# RJ45LVDS_SPI.net
KiCad netlist of a schematic drawn in EAGLE
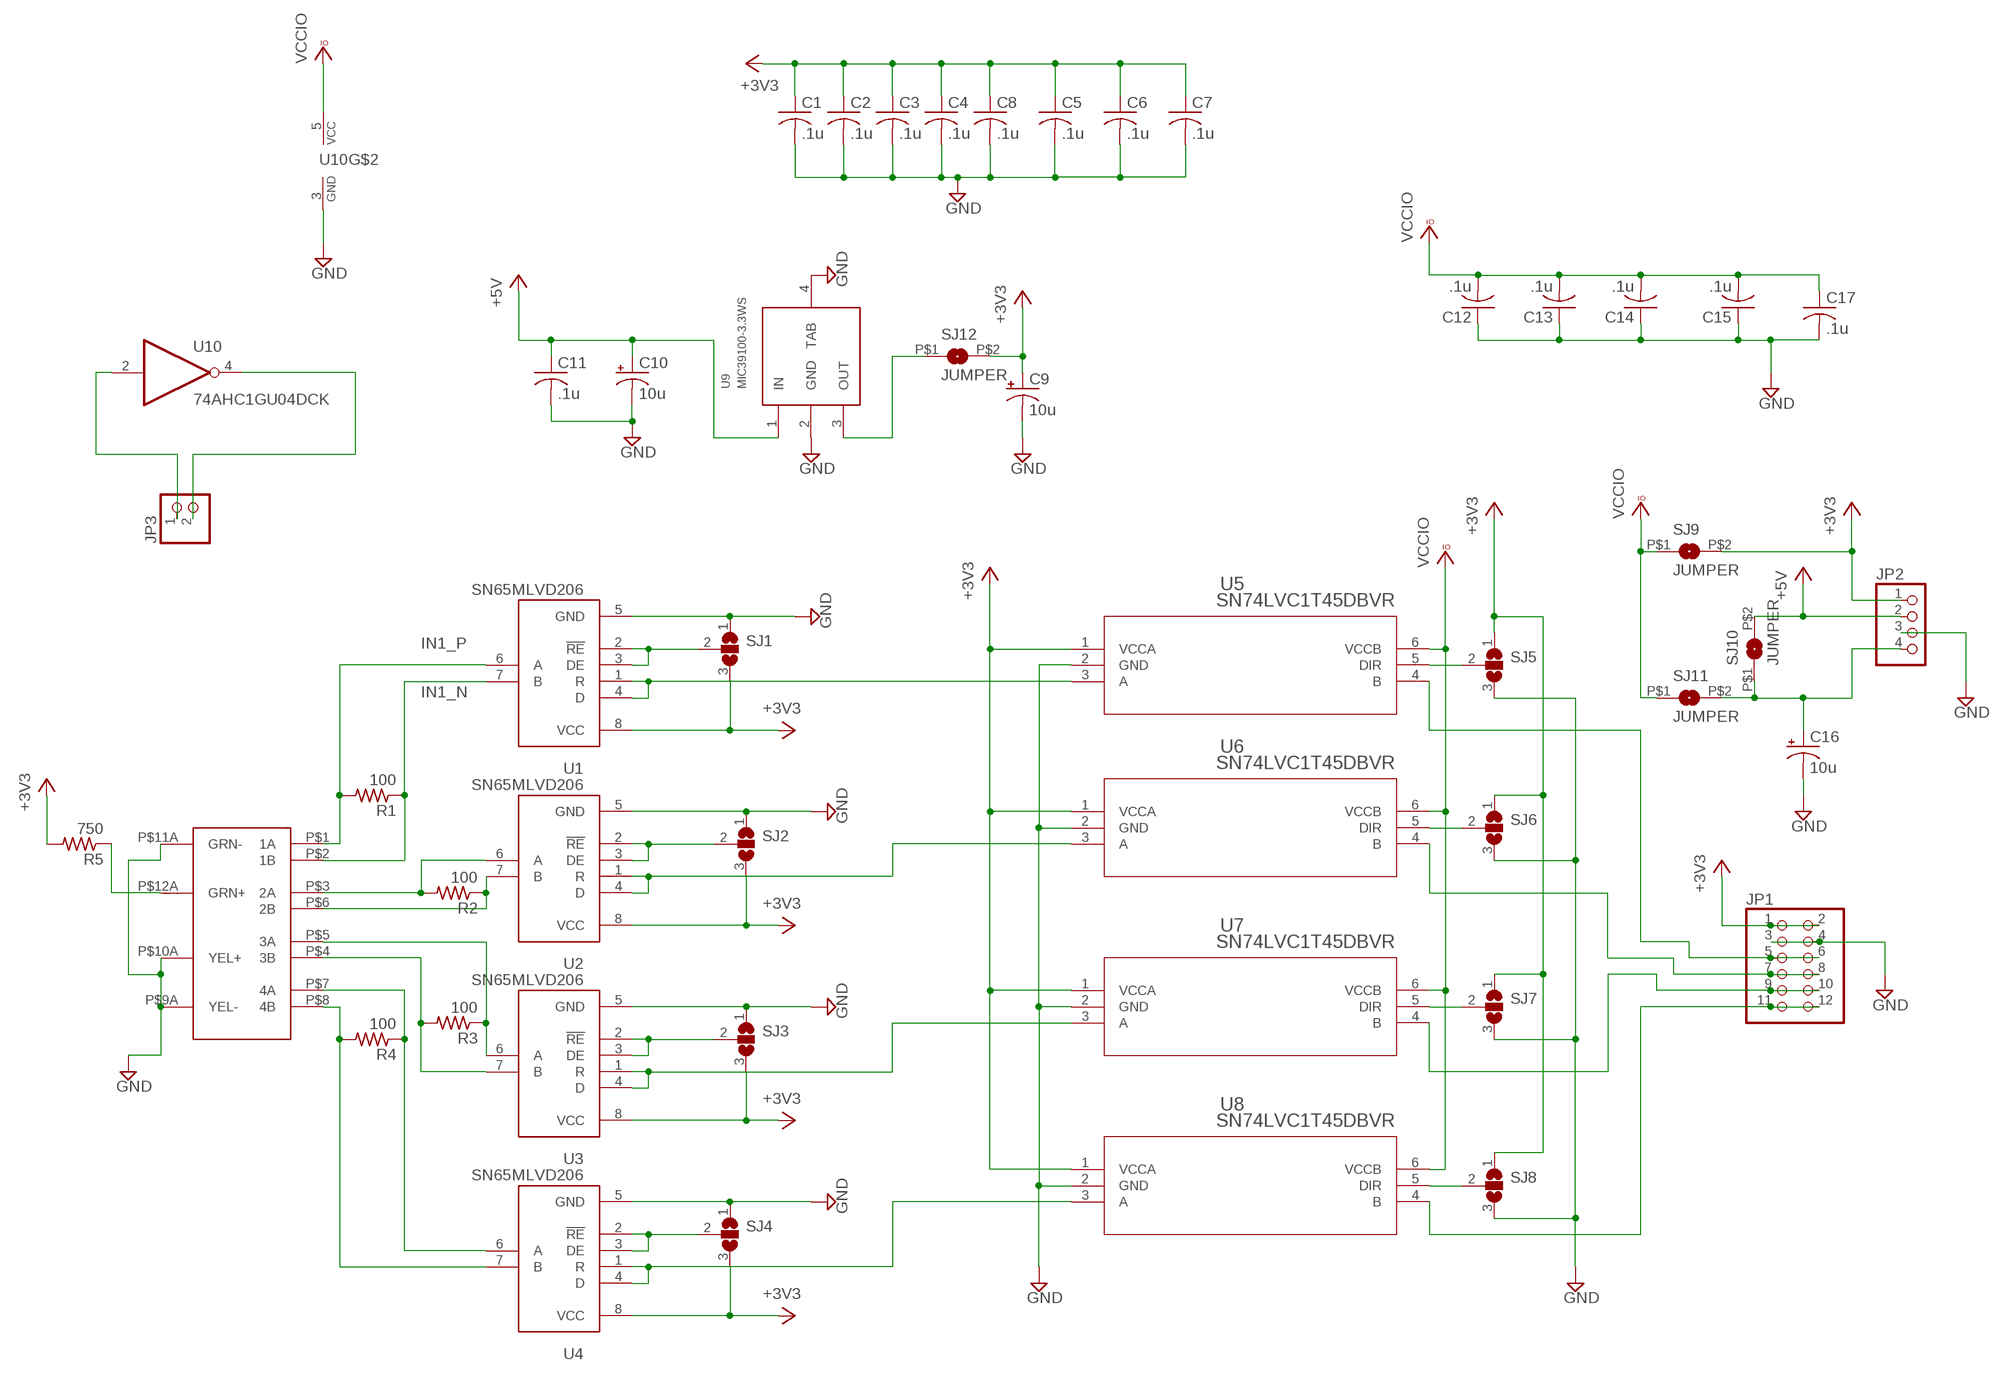
[diagram p0: schematic, sheet 1]

(export (version "E")
  (design (tool "Eeschema 10.0.6"))
  (components
    (comp (ref "C1")
      (value ".1u")
      (footprint "eagle-import:C0603")
      (libsource (lib "eagle-import") (part "C-USC0603"))
    )
    (comp (ref "C2")
      (value ".1u")
      (footprint "eagle-import:C0603")
      (libsource (lib "eagle-import") (part "C-USC0603"))
    )
    (comp (ref "C3")
      (value ".1u")
      (footprint "eagle-import:C0603")
      (libsource (lib "eagle-import") (part "C-USC0603"))
    )
    (comp (ref "C4")
      (value ".1u")
      (footprint "eagle-import:C0603")
      (libsource (lib "eagle-import") (part "C-USC0603"))
    )
    (comp (ref "C5")
      (value ".1u")
      (footprint "eagle-import:C0603")
      (libsource (lib "eagle-import") (part "C-USC0603"))
    )
    (comp (ref "C6")
      (value ".1u")
      (footprint "eagle-import:C0603")
      (libsource (lib "eagle-import") (part "C-USC0603"))
    )
    (comp (ref "C7")
      (value ".1u")
      (footprint "eagle-import:C0603")
      (libsource (lib "eagle-import") (part "C-USC0603"))
    )
    (comp (ref "C8")
      (value ".1u")
      (footprint "eagle-import:C0603")
      (libsource (lib "eagle-import") (part "C-USC0603"))
    )
    (comp (ref "C9")
      (value "10u")
      (footprint "eagle-import:SMC_B")
      (libsource (lib "eagle-import") (part "CPOL-USSMCB"))
    )
    (comp (ref "C10")
      (value "10u")
      (footprint "eagle-import:SMC_B")
      (libsource (lib "eagle-import") (part "CPOL-USSMCB"))
    )
    (comp (ref "C11")
      (value ".1u")
      (footprint "eagle-import:C0603")
      (libsource (lib "eagle-import") (part "C-USC0603"))
    )
    (comp (ref "C12")
      (value ".1u")
      (footprint "eagle-import:C0603")
      (libsource (lib "eagle-import") (part "C-USC0603"))
    )
    (comp (ref "C13")
      (value ".1u")
      (footprint "eagle-import:C0603")
      (libsource (lib "eagle-import") (part "C-USC0603"))
    )
    (comp (ref "C14")
      (value ".1u")
      (footprint "eagle-import:C0603")
      (libsource (lib "eagle-import") (part "C-USC0603"))
    )
    (comp (ref "C15")
      (value ".1u")
      (footprint "eagle-import:C0603")
      (libsource (lib "eagle-import") (part "C-USC0603"))
    )
    (comp (ref "C16")
      (value "10u")
      (footprint "eagle-import:SMC_B")
      (libsource (lib "eagle-import") (part "CPOL-USSMCB"))
    )
    (comp (ref "C17")
      (value ".1u")
      (footprint "eagle-import:C0603")
      (libsource (lib "eagle-import") (part "C-USC0603"))
    )
    (comp (ref "J1")
      (value "MRJ")
      (footprint "eagle-import:MRJ-MEGAMIX")
      (libsource (lib "eagle-import") (part "MRJ"))
    )
    (comp (ref "JP1")
      (value "PINHD-2X6")
      (footprint "eagle-import:2X06")
      (libsource (lib "eagle-import") (part "PINHD-2X6"))
    )
    (comp (ref "JP2")
      (value "PINHD-1X4")
      (footprint "eagle-import:1X04")
      (libsource (lib "eagle-import") (part "PINHD-1X4"))
    )
    (comp (ref "JP3")
      (value "PINHD-1X2")
      (footprint "eagle-import:1X02")
      (libsource (lib "eagle-import") (part "PINHD-1X2"))
    )
    (comp (ref "R1")
      (value "100")
      (footprint "eagle-import:R0603")
      (libsource (lib "eagle-import") (part "R-US_R0603"))
    )
    (comp (ref "R2")
      (value "100")
      (footprint "eagle-import:R0603")
      (libsource (lib "eagle-import") (part "R-US_R0603"))
    )
    (comp (ref "R3")
      (value "100")
      (footprint "eagle-import:R0603")
      (libsource (lib "eagle-import") (part "R-US_R0603"))
    )
    (comp (ref "R4")
      (value "100")
      (footprint "eagle-import:R0603")
      (libsource (lib "eagle-import") (part "R-US_R0603"))
    )
    (comp (ref "R5")
      (value "750")
      (footprint "eagle-import:R0603")
      (libsource (lib "eagle-import") (part "R-US_R0603"))
    )
    (comp (ref "SJ1")
      (value "SJ2W")
      (footprint "eagle-import:SJ_2")
      (libsource (lib "eagle-import") (part "SJ2W"))
    )
    (comp (ref "SJ2")
      (value "SJ2W")
      (footprint "eagle-import:SJ_2")
      (libsource (lib "eagle-import") (part "SJ2W"))
    )
    (comp (ref "SJ3")
      (value "SJ2W")
      (footprint "eagle-import:SJ_2")
      (libsource (lib "eagle-import") (part "SJ2W"))
    )
    (comp (ref "SJ4")
      (value "SJ2W")
      (footprint "eagle-import:SJ_2")
      (libsource (lib "eagle-import") (part "SJ2W"))
    )
    (comp (ref "SJ5")
      (value "SJ2W")
      (footprint "eagle-import:SJ_2")
      (libsource (lib "eagle-import") (part "SJ2W"))
    )
    (comp (ref "SJ6")
      (value "SJ2W")
      (footprint "eagle-import:SJ_2")
      (libsource (lib "eagle-import") (part "SJ2W"))
    )
    (comp (ref "SJ7")
      (value "SJ2W")
      (footprint "eagle-import:SJ_2")
      (libsource (lib "eagle-import") (part "SJ2W"))
    )
    (comp (ref "SJ8")
      (value "SJ2W")
      (footprint "eagle-import:SJ_2")
      (libsource (lib "eagle-import") (part "SJ2W"))
    )
    (comp (ref "SJ9")
      (value "JUMPER")
      (footprint "eagle-import:0603JMP")
      (libsource (lib "eagle-import") (part "JUMPER"))
    )
    (comp (ref "SJ10")
      (value "JUMPER")
      (footprint "eagle-import:0603JMP")
      (libsource (lib "eagle-import") (part "JUMPER"))
    )
    (comp (ref "SJ11")
      (value "JUMPER")
      (footprint "eagle-import:0603JMP")
      (libsource (lib "eagle-import") (part "JUMPER"))
    )
    (comp (ref "SJ12")
      (value "JUMPER")
      (footprint "eagle-import:0603JMP")
      (libsource (lib "eagle-import") (part "JUMPER"))
    )
    (comp (ref "U1")
      (value "SN65MLVD206")
      (footprint "eagle-import:SOIC08-FAIRCHILD")
      (libsource (lib "eagle-import") (part "SN65MLVD206"))
    )
    (comp (ref "U2")
      (value "SN65MLVD206")
      (footprint "eagle-import:SOIC08-FAIRCHILD")
      (libsource (lib "eagle-import") (part "SN65MLVD206"))
    )
    (comp (ref "U3")
      (value "SN65MLVD206")
      (footprint "eagle-import:SOIC08-FAIRCHILD")
      (libsource (lib "eagle-import") (part "SN65MLVD206"))
    )
    (comp (ref "U4")
      (value "SN65MLVD206")
      (footprint "eagle-import:SOIC08-FAIRCHILD")
      (libsource (lib "eagle-import") (part "SN65MLVD206"))
    )
    (comp (ref "U5")
      (value "SN74LVC1T45DBVR")
      (footprint "eagle-import:DBV6")
      (libsource (lib "eagle-import") (part "SN74LVC1T45DBVR"))
    )
    (comp (ref "U6")
      (value "SN74LVC1T45DBVR")
      (footprint "eagle-import:DBV6")
      (libsource (lib "eagle-import") (part "SN74LVC1T45DBVR"))
    )
    (comp (ref "U7")
      (value "SN74LVC1T45DBVR")
      (footprint "eagle-import:DBV6")
      (libsource (lib "eagle-import") (part "SN74LVC1T45DBVR"))
    )
    (comp (ref "U8")
      (value "SN74LVC1T45DBVR")
      (footprint "eagle-import:DBV6")
      (libsource (lib "eagle-import") (part "SN74LVC1T45DBVR"))
    )
    (comp (ref "U9")
      (value "MIC39100-3.3WS")
      (footprint "eagle-import:SOT223")
      (libsource (lib "eagle-import") (part "MIC37100"))
    )
    (comp (ref "U10")
      (value "74AHC1GU04DCK")
      (footprint "eagle-import:SC70-5")
      (libsource (lib "eagle-import") (part "741GU04DCKAHC"))
    )
  )
  (nets
    (net (code "1") (name "+3V3") (class "Default")
      (node (ref "C1") (pin "1") (pinfunction "1_1") (pintype "passive"))
      (node (ref "C2") (pin "1") (pinfunction "1_1") (pintype "passive"))
      (node (ref "C3") (pin "1") (pinfunction "1_1") (pintype "passive"))
      (node (ref "C4") (pin "1") (pinfunction "1_1") (pintype "passive"))
      (node (ref "C5") (pin "1") (pinfunction "1_1") (pintype "passive"))
      (node (ref "C6") (pin "1") (pinfunction "1_1") (pintype "passive"))
      (node (ref "C7") (pin "1") (pinfunction "1_1") (pintype "passive"))
      (node (ref "C8") (pin "1") (pinfunction "1_1") (pintype "passive"))
      (node (ref "C9") (pin "+") (pinfunction "+_+") (pintype "passive"))
      (node (ref "JP1") (pin "1") (pinfunction "1_1") (pintype "passive"))
      (node (ref "JP1") (pin "2") (pinfunction "2_2") (pintype "passive"))
      (node (ref "JP2") (pin "1") (pinfunction "1_1") (pintype "passive"))
      (node (ref "R5") (pin "2") (pinfunction "2_2") (pintype "passive"))
      (node (ref "SJ1") (pin "3") (pinfunction "3_3") (pintype "passive"))
      (node (ref "SJ12") (pin "P$2") (pinfunction "2_P$2") (pintype "passive"))
      (node (ref "SJ2") (pin "3") (pinfunction "3_3") (pintype "passive"))
      (node (ref "SJ3") (pin "3") (pinfunction "3_3") (pintype "passive"))
      (node (ref "SJ4") (pin "3") (pinfunction "3_3") (pintype "passive"))
      (node (ref "SJ5") (pin "1") (pinfunction "1_1") (pintype "passive"))
      (node (ref "SJ6") (pin "1") (pinfunction "1_1") (pintype "passive"))
      (node (ref "SJ7") (pin "1") (pinfunction "1_1") (pintype "passive"))
      (node (ref "SJ8") (pin "1") (pinfunction "1_1") (pintype "passive"))
      (node (ref "SJ9") (pin "P$2") (pinfunction "2_P$2") (pintype "passive"))
      (node (ref "U1") (pin "8") (pinfunction "VCC_8") (pintype "bidirectional"))
      (node (ref "U2") (pin "8") (pinfunction "VCC_8") (pintype "bidirectional"))
      (node (ref "U3") (pin "8") (pinfunction "VCC_8") (pintype "bidirectional"))
      (node (ref "U4") (pin "8") (pinfunction "VCC_8") (pintype "bidirectional"))
      (node (ref "U5") (pin "1") (pinfunction "VCCA_1") (pintype "power_in"))
      (node (ref "U6") (pin "1") (pinfunction "VCCA_1") (pintype "power_in"))
      (node (ref "U7") (pin "1") (pinfunction "VCCA_1") (pintype "power_in"))
      (node (ref "U8") (pin "1") (pinfunction "VCCA_1") (pintype "power_in"))
    )
    (net (code "2") (name "+5V") (class "Default")
      (node (ref "C10") (pin "+") (pinfunction "+_+") (pintype "passive"))
      (node (ref "C11") (pin "1") (pinfunction "1_1") (pintype "passive"))
      (node (ref "JP2") (pin "2") (pinfunction "2_2") (pintype "passive"))
      (node (ref "SJ10") (pin "P$2") (pinfunction "2_P$2") (pintype "passive"))
      (node (ref "U9") (pin "1") (pinfunction "IN_1") (pintype "bidirectional"))
    )
    (net (code "3") (name "/IN1_N") (class "Default")
      (node (ref "J1") (pin "P$2") (pinfunction "1B_P$2") (pintype "bidirectional"))
      (node (ref "R1") (pin "1") (pinfunction "1_1") (pintype "passive"))
      (node (ref "U1") (pin "7") (pinfunction "B_7") (pintype "bidirectional"))
    )
    (net (code "4") (name "/IN1_P") (class "Default")
      (node (ref "J1") (pin "P$1") (pinfunction "1A_P$1") (pintype "bidirectional"))
      (node (ref "R1") (pin "2") (pinfunction "2_2") (pintype "passive"))
      (node (ref "U1") (pin "6") (pinfunction "A_6") (pintype "bidirectional"))
    )
    (net (code "5") (name "GND") (class "Default")
      (node (ref "C1") (pin "2") (pinfunction "2_2") (pintype "passive"))
      (node (ref "C10") (pin "-") (pinfunction "-_-") (pintype "passive"))
      (node (ref "C11") (pin "2") (pinfunction "2_2") (pintype "passive"))
      (node (ref "C12") (pin "1") (pinfunction "1_1") (pintype "passive"))
      (node (ref "C13") (pin "1") (pinfunction "1_1") (pintype "passive"))
      (node (ref "C14") (pin "1") (pinfunction "1_1") (pintype "passive"))
      (node (ref "C15") (pin "1") (pinfunction "1_1") (pintype "passive"))
      (node (ref "C16") (pin "-") (pinfunction "-_-") (pintype "passive"))
      (node (ref "C17") (pin "2") (pinfunction "2_2") (pintype "passive"))
      (node (ref "C2") (pin "2") (pinfunction "2_2") (pintype "passive"))
      (node (ref "C3") (pin "2") (pinfunction "2_2") (pintype "passive"))
      (node (ref "C4") (pin "2") (pinfunction "2_2") (pintype "passive"))
      (node (ref "C5") (pin "2") (pinfunction "2_2") (pintype "passive"))
      (node (ref "C6") (pin "2") (pinfunction "2_2") (pintype "passive"))
      (node (ref "C7") (pin "2") (pinfunction "2_2") (pintype "passive"))
      (node (ref "C8") (pin "2") (pinfunction "2_2") (pintype "passive"))
      (node (ref "C9") (pin "-") (pinfunction "-_-") (pintype "passive"))
      (node (ref "J1") (pin "P$10A") (pinfunction "YEL+_P$10A") (pintype "bidirectional"))
      (node (ref "J1") (pin "P$11A") (pinfunction "GRN-_P$11A") (pintype "bidirectional"))
      (node (ref "J1") (pin "P$9A") (pinfunction "YEL-_P$9A") (pintype "bidirectional"))
      (node (ref "JP1") (pin "3") (pinfunction "3_3") (pintype "passive"))
      (node (ref "JP1") (pin "4") (pinfunction "4_4") (pintype "passive"))
      (node (ref "JP2") (pin "3") (pinfunction "3_3") (pintype "passive"))
      (node (ref "SJ1") (pin "1") (pinfunction "1_1") (pintype "passive"))
      (node (ref "SJ2") (pin "1") (pinfunction "1_1") (pintype "passive"))
      (node (ref "SJ3") (pin "1") (pinfunction "1_1") (pintype "passive"))
      (node (ref "SJ4") (pin "1") (pinfunction "1_1") (pintype "passive"))
      (node (ref "SJ5") (pin "3") (pinfunction "3_3") (pintype "passive"))
      (node (ref "SJ6") (pin "3") (pinfunction "3_3") (pintype "passive"))
      (node (ref "SJ7") (pin "3") (pinfunction "3_3") (pintype "passive"))
      (node (ref "SJ8") (pin "3") (pinfunction "3_3") (pintype "passive"))
      (node (ref "U1") (pin "5") (pinfunction "GND_5") (pintype "bidirectional"))
      (node (ref "U10") (pin "3") (pinfunction "GND_3") (pintype "power_in"))
      (node (ref "U2") (pin "5") (pinfunction "GND_5") (pintype "bidirectional"))
      (node (ref "U3") (pin "5") (pinfunction "GND_5") (pintype "bidirectional"))
      (node (ref "U4") (pin "5") (pinfunction "GND_5") (pintype "bidirectional"))
      (node (ref "U5") (pin "2") (pinfunction "GND_2") (pintype "power_in"))
      (node (ref "U6") (pin "2") (pinfunction "GND_2") (pintype "power_in"))
      (node (ref "U7") (pin "2") (pinfunction "GND_2") (pintype "power_in"))
      (node (ref "U8") (pin "2") (pinfunction "GND_2") (pintype "power_in"))
      (node (ref "U9") (pin "2") (pinfunction "GND_2") (pintype "bidirectional"))
      (node (ref "U9") (pin "4") (pinfunction "TAB_4") (pintype "bidirectional"))
    )
    (net (code "6") (name "Net-(J1-2A)") (class "Default")
      (node (ref "J1") (pin "P$3") (pinfunction "2A_P$3") (pintype "bidirectional"))
      (node (ref "R2") (pin "2") (pinfunction "2_2") (pintype "passive"))
      (node (ref "U2") (pin "6") (pinfunction "A_6") (pintype "bidirectional"))
    )
    (net (code "7") (name "Net-(J1-2B)") (class "Default")
      (node (ref "J1") (pin "P$6") (pinfunction "2B_P$6") (pintype "bidirectional"))
      (node (ref "R2") (pin "1") (pinfunction "1_1") (pintype "passive"))
      (node (ref "U2") (pin "7") (pinfunction "B_7") (pintype "bidirectional"))
    )
    (net (code "8") (name "Net-(J1-3A)") (class "Default")
      (node (ref "J1") (pin "P$5") (pinfunction "3A_P$5") (pintype "bidirectional"))
      (node (ref "R3") (pin "1") (pinfunction "1_1") (pintype "passive"))
      (node (ref "U3") (pin "6") (pinfunction "A_6") (pintype "bidirectional"))
    )
    (net (code "9") (name "Net-(J1-3B)") (class "Default")
      (node (ref "J1") (pin "P$4") (pinfunction "3B_P$4") (pintype "bidirectional"))
      (node (ref "R3") (pin "2") (pinfunction "2_2") (pintype "passive"))
      (node (ref "U3") (pin "7") (pinfunction "B_7") (pintype "bidirectional"))
    )
    (net (code "10") (name "Net-(J1-4A)") (class "Default")
      (node (ref "J1") (pin "P$7") (pinfunction "4A_P$7") (pintype "bidirectional"))
      (node (ref "R4") (pin "1") (pinfunction "1_1") (pintype "passive"))
      (node (ref "U4") (pin "6") (pinfunction "A_6") (pintype "bidirectional"))
    )
    (net (code "11") (name "Net-(J1-4B)") (class "Default")
      (node (ref "J1") (pin "P$8") (pinfunction "4B_P$8") (pintype "bidirectional"))
      (node (ref "R4") (pin "2") (pinfunction "2_2") (pintype "passive"))
      (node (ref "U4") (pin "7") (pinfunction "B_7") (pintype "bidirectional"))
    )
    (net (code "12") (name "Net-(J1-GRN+)") (class "Default")
      (node (ref "J1") (pin "P$12A") (pinfunction "GRN+_P$12A") (pintype "bidirectional"))
      (node (ref "R5") (pin "1") (pinfunction "1_1") (pintype "passive"))
    )
    (net (code "13") (name "Net-(SJ10-1)") (class "Default")
      (node (ref "C16") (pin "+") (pinfunction "+_+") (pintype "passive"))
      (node (ref "JP2") (pin "4") (pinfunction "4_4") (pintype "passive"))
      (node (ref "SJ10") (pin "P$1") (pinfunction "1_P$1") (pintype "passive"))
      (node (ref "SJ11") (pin "P$2") (pinfunction "2_P$2") (pintype "passive"))
    )
    (net (code "14") (name "Net-(SJ12-1)") (class "Default")
      (node (ref "SJ12") (pin "P$1") (pinfunction "1_P$1") (pintype "passive"))
      (node (ref "U9") (pin "3") (pinfunction "OUT_3") (pintype "bidirectional"))
    )
    (net (code "15") (name "Net-(U1-D)") (class "Default")
      (node (ref "U1") (pin "1") (pinfunction "R_1") (pintype "bidirectional"))
      (node (ref "U1") (pin "4") (pinfunction "D_4") (pintype "bidirectional"))
      (node (ref "U5") (pin "3") (pinfunction "A_3") (pintype "input"))
    )
    (net (code "16") (name "Net-(U1-DE)") (class "Default")
      (node (ref "SJ1") (pin "2") (pinfunction "2_2") (pintype "passive"))
      (node (ref "U1") (pin "2") (pinfunction "~{RE}_2") (pintype "bidirectional"))
      (node (ref "U1") (pin "3") (pinfunction "DE_3") (pintype "bidirectional"))
    )
    (net (code "17") (name "Net-(U2-D)") (class "Default")
      (node (ref "U2") (pin "1") (pinfunction "R_1") (pintype "bidirectional"))
      (node (ref "U2") (pin "4") (pinfunction "D_4") (pintype "bidirectional"))
      (node (ref "U6") (pin "3") (pinfunction "A_3") (pintype "input"))
    )
    (net (code "18") (name "Net-(U2-DE)") (class "Default")
      (node (ref "SJ2") (pin "2") (pinfunction "2_2") (pintype "passive"))
      (node (ref "U2") (pin "2") (pinfunction "~{RE}_2") (pintype "bidirectional"))
      (node (ref "U2") (pin "3") (pinfunction "DE_3") (pintype "bidirectional"))
    )
    (net (code "19") (name "Net-(U3-D)") (class "Default")
      (node (ref "U3") (pin "1") (pinfunction "R_1") (pintype "bidirectional"))
      (node (ref "U3") (pin "4") (pinfunction "D_4") (pintype "bidirectional"))
      (node (ref "U7") (pin "3") (pinfunction "A_3") (pintype "input"))
    )
    (net (code "20") (name "Net-(U3-DE)") (class "Default")
      (node (ref "SJ3") (pin "2") (pinfunction "2_2") (pintype "passive"))
      (node (ref "U3") (pin "2") (pinfunction "~{RE}_2") (pintype "bidirectional"))
      (node (ref "U3") (pin "3") (pinfunction "DE_3") (pintype "bidirectional"))
    )
    (net (code "21") (name "Net-(U4-D)") (class "Default")
      (node (ref "U4") (pin "1") (pinfunction "R_1") (pintype "bidirectional"))
      (node (ref "U4") (pin "4") (pinfunction "D_4") (pintype "bidirectional"))
      (node (ref "U8") (pin "3") (pinfunction "A_3") (pintype "input"))
    )
    (net (code "22") (name "Net-(U4-DE)") (class "Default")
      (node (ref "SJ4") (pin "2") (pinfunction "2_2") (pintype "passive"))
      (node (ref "U4") (pin "2") (pinfunction "~{RE}_2") (pintype "bidirectional"))
      (node (ref "U4") (pin "3") (pinfunction "DE_3") (pintype "bidirectional"))
    )
    (net (code "23") (name "Net-(U5-B)") (class "Default")
      (node (ref "JP1") (pin "5") (pinfunction "5_5") (pintype "passive"))
      (node (ref "JP1") (pin "6") (pinfunction "6_6") (pintype "passive"))
      (node (ref "U5") (pin "4") (pinfunction "B_4") (pintype "input"))
    )
    (net (code "24") (name "Net-(U5-DIR)") (class "Default")
      (node (ref "SJ5") (pin "2") (pinfunction "2_2") (pintype "passive"))
      (node (ref "U5") (pin "5") (pinfunction "DIR_5") (pintype "input"))
    )
    (net (code "25") (name "Net-(U6-B)") (class "Default")
      (node (ref "JP1") (pin "7") (pinfunction "7_7") (pintype "passive"))
      (node (ref "JP1") (pin "8") (pinfunction "8_8") (pintype "passive"))
      (node (ref "U6") (pin "4") (pinfunction "B_4") (pintype "input"))
    )
    (net (code "26") (name "Net-(U6-DIR)") (class "Default")
      (node (ref "SJ6") (pin "2") (pinfunction "2_2") (pintype "passive"))
      (node (ref "U6") (pin "5") (pinfunction "DIR_5") (pintype "input"))
    )
    (net (code "27") (name "Net-(U7-B)") (class "Default")
      (node (ref "JP1") (pin "10") (pinfunction "10_10") (pintype "passive"))
      (node (ref "JP1") (pin "9") (pinfunction "9_9") (pintype "passive"))
      (node (ref "U7") (pin "4") (pinfunction "B_4") (pintype "input"))
    )
    (net (code "28") (name "Net-(U7-DIR)") (class "Default")
      (node (ref "SJ7") (pin "2") (pinfunction "2_2") (pintype "passive"))
      (node (ref "U7") (pin "5") (pinfunction "DIR_5") (pintype "input"))
    )
    (net (code "29") (name "Net-(U8-B)") (class "Default")
      (node (ref "JP1") (pin "11") (pinfunction "11_11") (pintype "passive"))
      (node (ref "JP1") (pin "12") (pinfunction "12_12") (pintype "passive"))
      (node (ref "U8") (pin "4") (pinfunction "B_4") (pintype "input"))
    )
    (net (code "30") (name "Net-(U8-DIR)") (class "Default")
      (node (ref "SJ8") (pin "2") (pinfunction "2_2") (pintype "passive"))
      (node (ref "U8") (pin "5") (pinfunction "DIR_5") (pintype "input"))
    )
    (net (code "31") (name "Net-(U10A-I)") (class "Default")
      (node (ref "JP3") (pin "1") (pinfunction "1_1") (pintype "passive"))
      (node (ref "U10") (pin "2") (pinfunction "I_2") (pintype "input"))
    )
    (net (code "32") (name "Net-(U10A-O)") (class "Default")
      (node (ref "JP3") (pin "2") (pinfunction "2_2") (pintype "passive"))
      (node (ref "U10") (pin "4") (pinfunction "O_4") (pintype "output"))
    )
    (net (code "33") (name "VCCIO") (class "Default")
      (node (ref "C12") (pin "2") (pinfunction "2_2") (pintype "passive"))
      (node (ref "C13") (pin "2") (pinfunction "2_2") (pintype "passive"))
      (node (ref "C14") (pin "2") (pinfunction "2_2") (pintype "passive"))
      (node (ref "C15") (pin "2") (pinfunction "2_2") (pintype "passive"))
      (node (ref "C17") (pin "1") (pinfunction "1_1") (pintype "passive"))
      (node (ref "SJ11") (pin "P$1") (pinfunction "1_P$1") (pintype "passive"))
      (node (ref "SJ9") (pin "P$1") (pinfunction "1_P$1") (pintype "passive"))
      (node (ref "U10") (pin "5") (pinfunction "VCC_5") (pintype "power_in"))
      (node (ref "U5") (pin "6") (pinfunction "VCCB_6") (pintype "power_in"))
      (node (ref "U6") (pin "6") (pinfunction "VCCB_6") (pintype "power_in"))
      (node (ref "U7") (pin "6") (pinfunction "VCCB_6") (pintype "power_in"))
      (node (ref "U8") (pin "6") (pinfunction "VCCB_6") (pintype "power_in"))
    )
  )
)
